# 5_Sensors.net
KiCad netlist of a schematic drawn in Altium Designer
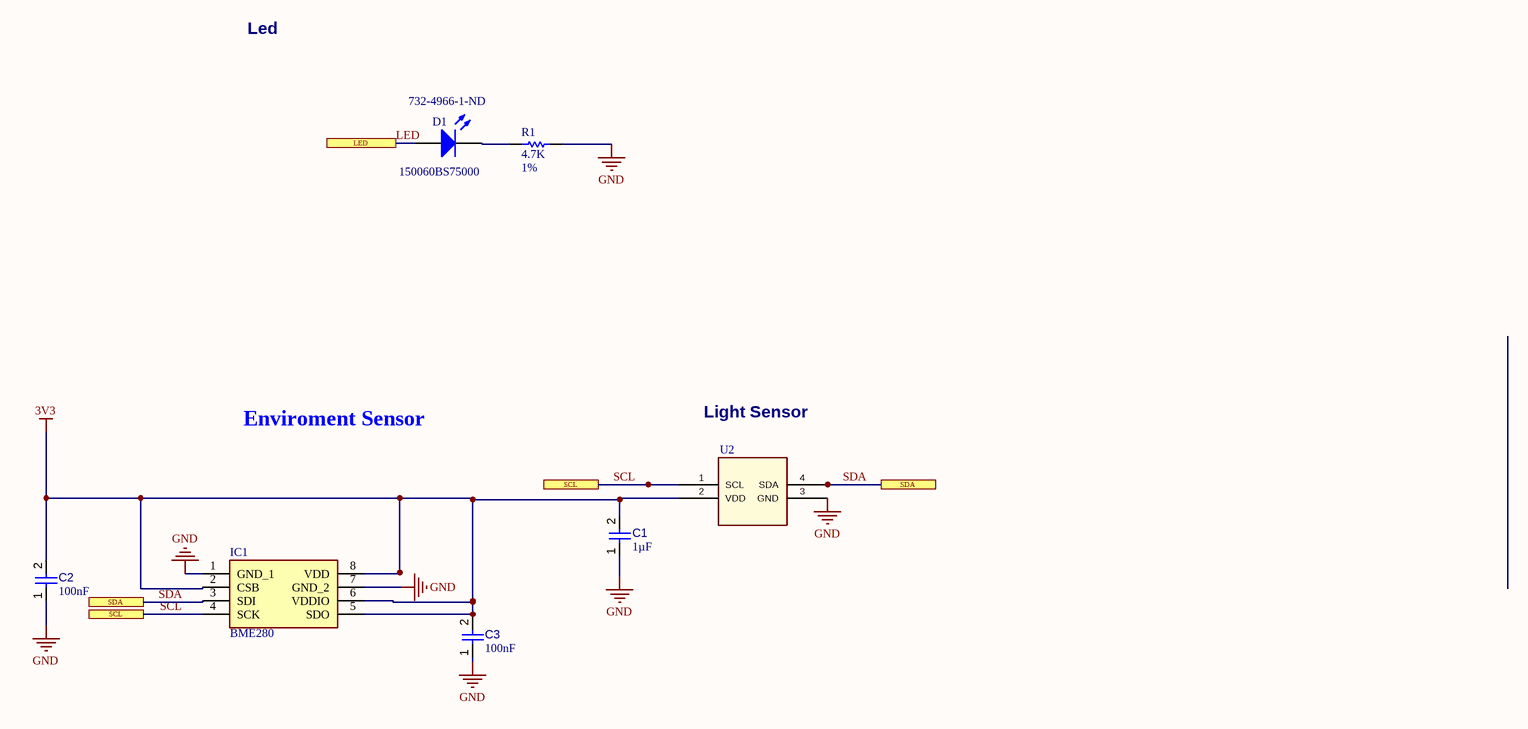
[diagram p0: [5] Sensors.SchDoc]

(export (version "E")
  (design (tool "Eeschema 10.0.6"))
  (components
    (comp (ref "C1")
      (value "1µF")
      (footprint "CAPC1608X90X40ML10T20")
      (description "Chip Capacitor, 1 uF, +/- 10%, 25 V, 0603 (1608 Metric)")
      (fields (field (name "TOLERANCE") "10%") (field (name "Comment") "Capacitor 1 uF +/- 10% 25 V 0603"))
      (libsource (lib "Latium Technologies") (part "CAP-NP-2"))
    )
    (comp (ref "C2")
      (value "100nF")
      (footprint "CAPC1608X90X40ML10T20")
      (description "Chip Capacitor, 100 nF, +/- 10%, 50 V, 0603 (1608 Metric)")
      (fields (field (name "TOLERANCE") "10%") (field (name "Comment") "Capacitor 100 nF +/-10% 50 V 0603"))
      (libsource (lib "Latium Technologies") (part "CAP-NP-2"))
    )
    (comp (ref "C3")
      (value "100nF")
      (footprint "CAPC1608X90X40ML10T20")
      (description "Chip Capacitor, 100 nF, +/- 10%, 50 V, 0603 (1608 Metric)")
      (fields (field (name "TOLERANCE") "10%") (field (name "Comment") "Capacitor 100 nF +/-10% 50 V 0603"))
      (libsource (lib "Latium Technologies") (part "CAP-NP-2"))
    )
    (comp (ref "D1")
      (value "LED")
      (footprint "LED BLUE CLEAR [0603]")
      (description "LED BLUE CLEAR 0603 SMD")
      (fields (field (name "SUPPLIER PART NUMBER 1") "732-4966-1-ND") (field (name "PN") "150060BS75000"))
      (libsource (lib "MasterLib") (part "LED BLUE CLEAR 0603 SMD"))
    )
    (comp (ref "IC1")
      (value "BME280")
      (footprint "Sensor housing 8-pin LGA")
      (description "Integrated Circuit")
      (fields
        (field (name "MANUFACTURER_PART_NUMBER") "BME680")
        (field (name "MOUSER PART NUMBER") "262-BME680")
      )
      (libsource (lib "MasterLib") (part "BME680"))
    )
    (comp (ref "R1")
      (value "RES 4.7K 1% 0.1W [0603]")
      (footprint "RES 0603")
      (fields (field (name "RESISTANCE") "4.7K") (field (name "TOLERANCE") "1%"))
      (libsource (lib "MasterLib") (part "RES 4.7K 1% [0603]"))
    )
    (comp (ref "U2")
      (value "VEML7700-TR")
      (footprint "Ambient Light Sensor with I2C")
      (description "Ambient Light Sensor with I2C")
      (libsource (lib "MasterLib") (part "Ambient Light Sensor I2C"))
    )
  )
  (nets
    (net (code "1") (name "/LED") (class "Default")
      (node (ref "D1") (pin "2") (pinfunction "2_2") (pintype "passive"))
    )
    (net (code "2") (name "/SCL") (class "Default")
      (node (ref "IC1") (pin "4") (pinfunction "SCK_4") (pintype "passive"))
      (node (ref "U2") (pin "1") (pinfunction "SCL_1") (pintype "passive"))
    )
    (net (code "3") (name "/SDA") (class "Default")
      (node (ref "IC1") (pin "3") (pinfunction "SDI_3") (pintype "passive"))
      (node (ref "U2") (pin "4") (pinfunction "SDA_4") (pintype "passive"))
    )
    (net (code "4") (name "3V3") (class "Default")
      (node (ref "C1") (pin "2") (pinfunction "2_2") (pintype "passive"))
      (node (ref "C2") (pin "2") (pinfunction "2_2") (pintype "passive"))
      (node (ref "C3") (pin "2") (pinfunction "2_2") (pintype "passive"))
      (node (ref "IC1") (pin "2") (pinfunction "CSB_2") (pintype "passive"))
      (node (ref "IC1") (pin "5") (pinfunction "SDO_5") (pintype "passive"))
      (node (ref "IC1") (pin "6") (pinfunction "VDDIO_6") (pintype "passive"))
      (node (ref "IC1") (pin "8") (pinfunction "VDD_8") (pintype "passive"))
      (node (ref "U2") (pin "2") (pinfunction "VDD_2") (pintype "power_in"))
    )
    (net (code "5") (name "GND") (class "Default")
      (node (ref "C1") (pin "1") (pinfunction "1_1") (pintype "passive"))
      (node (ref "C2") (pin "1") (pinfunction "1_1") (pintype "passive"))
      (node (ref "C3") (pin "1") (pinfunction "1_1") (pintype "passive"))
      (node (ref "IC1") (pin "1") (pinfunction "GND_1_1") (pintype "passive"))
      (node (ref "IC1") (pin "7") (pinfunction "GND_2_7") (pintype "passive"))
      (node (ref "R1") (pin "2") (pinfunction "2_2") (pintype "passive"))
      (node (ref "U2") (pin "3") (pinfunction "GND_3") (pintype "power_in"))
    )
    (net (code "6") (name "Net-(D1-Pad1)") (class "Default")
      (node (ref "D1") (pin "1") (pinfunction "1_1") (pintype "passive"))
      (node (ref "R1") (pin "1") (pinfunction "1_1") (pintype "passive"))
    )
  )
)
